# Sheet1.net
KiCad netlist of a schematic drawn in Altium Designer
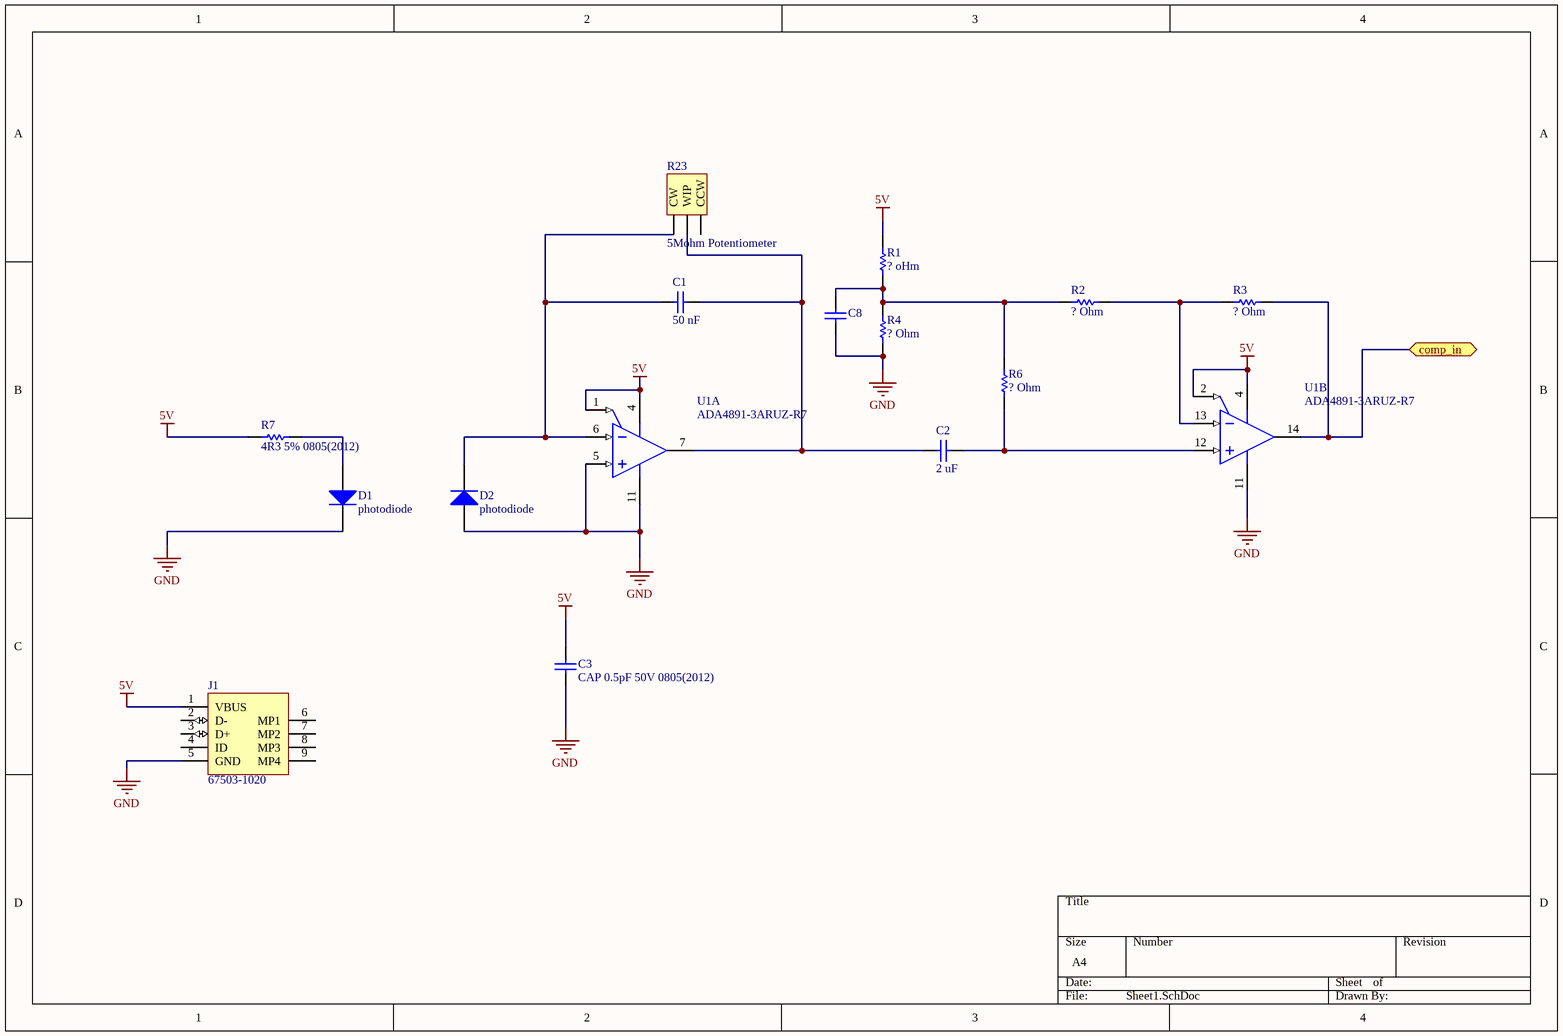
[diagram p0: Sheet1.SchDoc]

(export (version "E")
  (design (tool "Eeschema 10.0.6"))
  (components
    (comp (ref "C1")
      (value "50 nF")
      (footprint "CAPC0805(2012)75_M")
      (description "CAP 0.5pF 50V ±0.1pF 0805 (2012 Metric) Thickness 0.75mm SMD")
      (fields (field (name "TOLERANCE") "Â±0.1pF"))
      (libsource (lib "Altium Content Vault") (part "CMP-1036-00018-1"))
    )
    (comp (ref "C2")
      (value "2 uF")
      (footprint "CAPC0805(2012)75_M")
      (description "CAP 0.5pF 50V ±0.1pF 0805 (2012 Metric) Thickness 0.75mm SMD")
      (fields (field (name "TOLERANCE") "Â±0.1pF"))
      (libsource (lib "Altium Content Vault") (part "CMP-1036-00018-1"))
    )
    (comp (ref "C3")
      (value "CAP 0.5pF 50V 0805(2012)")
      (footprint "CAPC0805(2012)75_M")
      (description "CAP 0.5pF 50V ±0.1pF 0805 (2012 Metric) Thickness 0.75mm SMD")
      (fields (field (name "TOLERANCE") "Â±0.1pF"))
      (libsource (lib "Altium Content Vault") (part "CAP"))
    )
    (comp (ref "C8")
      (value "CAP 0.5pF 50V 0805(2012)")
      (footprint "CAPC0805(2012)75_M")
      (description "CAP 0.5pF 50V ±0.1pF 0805 (2012 Metric) Thickness 0.75mm SMD")
      (fields (field (name "TOLERANCE") "Â±0.1pF"))
      (libsource (lib "Altium Content Vault") (part "CMP-1036-00018-1"))
    )
    (comp (ref "D1")
      (value "photodiode")
      (footprint "3mm_diode")
      (libsource (lib "HeartbeatLibrary") (part "photodiode"))
    )
    (comp (ref "D2")
      (value "photodiode")
      (footprint "3mm_diode")
      (libsource (lib "HeartbeatLibrary") (part "photodiode"))
    )
    (comp (ref "J1")
      (value "67503-1020")
      (footprint "MOLX-67503-1020_V")
      (description "USB, MINI, SMD, RA KME04-USBMU03A01")
      (fields (field (name "MANUFACTURER") "Molex"))
      (libsource (lib "Altium Content Vault") (part "MOLX-67503-1020"))
    )
    (comp (ref "R1")
      (value "? oHm")
      (footprint "RESC0805(2012)_M")
      (description "4R3 0.125W 5% 0805 (2012 Metric)  SMD")
      (fields (field (name "TOLERANCE") "5 %") (field (name "POWER") "0.125 W"))
      (libsource (lib "Altium Content Vault") (part "RES"))
    )
    (comp (ref "R2")
      (value "? Ohm")
      (footprint "RESC0805(2012)_M")
      (description "4R3 0.125W 5% 0805 (2012 Metric)  SMD")
      (fields (field (name "TOLERANCE") "5 %") (field (name "POWER") "0.125 W"))
      (libsource (lib "Altium Content Vault") (part "RES"))
    )
    (comp (ref "R3")
      (value "? Ohm")
      (footprint "RESC0805(2012)_M")
      (description "4R3 0.125W 5% 0805 (2012 Metric)  SMD")
      (fields (field (name "TOLERANCE") "5 %") (field (name "POWER") "0.125 W"))
      (libsource (lib "Altium Content Vault") (part "CMP-1013-00017-1"))
    )
    (comp (ref "R4")
      (value "? Ohm")
      (footprint "RESC0805(2012)_M")
      (description "4R3 0.125W 5% 0805 (2012 Metric)  SMD")
      (fields (field (name "TOLERANCE") "5 %") (field (name "POWER") "0.125 W"))
      (libsource (lib "Altium Content Vault") (part "RES"))
    )
    (comp (ref "R6")
      (value "? Ohm")
      (footprint "RESC0805(2012)_M")
      (description "4R3 0.125W 5% 0805 (2012 Metric)  SMD")
      (fields (field (name "TOLERANCE") "5 %") (field (name "POWER") "0.125 W"))
      (libsource (lib "Altium Content Vault") (part "RES"))
    )
    (comp (ref "R7")
      (value "4R3 5% 0805(2012)")
      (footprint "RESC0805(2012)_M")
      (description "4R3 0.125W 5% 0805 (2012 Metric)  SMD")
      (fields (field (name "TOLERANCE") "5 %") (field (name "POWER") "0.125 W"))
      (libsource (lib "Altium Content Vault") (part "RES"))
    )
    (comp (ref "R23")
      (value "5Mohm Potentiometer")
      (footprint "5k_pot")
      (description "3296W-1-505LF")
      (libsource (lib "HeartbeatLibrary") (part "5Mohm Potentiometer"))
    )
    (comp (ref "U1")
      (value "ADA4891-3ARUZ-R7")
      (footprint "ADI-RU-14_L")
      (fields (field (name "GENERIC PART NUMBER") "ADA4891-3") (field (name "MANUFACTURER") "Analog Devices"))
      (libsource (lib "Altium Content Vault") (part "CMP-0384-01869-1"))
    )
  )
  (nets
    (net (code "1") (name "/comp_in") (class "Default")
      (node (ref "R3") (pin "2") (pinfunction "2_2") (pintype "passive"))
      (node (ref "U1") (pin "14") (pinfunction "OUT_2_14") (pintype "tri_state"))
    )
    (net (code "2") (name "5V") (class "Default")
      (node (ref "C3") (pin "2") (pinfunction "2_2") (pintype "passive"))
      (node (ref "J1") (pin "1") (pinfunction "VBUS_1") (pintype "power_in"))
      (node (ref "R1") (pin "2") (pinfunction "2_2") (pintype "passive"))
      (node (ref "R7") (pin "2") (pinfunction "2_2") (pintype "passive"))
      (node (ref "U1") (pin "1") (pinfunction "~{PD1}_1") (pintype "input"))
      (node (ref "U1") (pin "2") (pinfunction "~{PD2}_2") (pintype "input"))
      (node (ref "U1") (pin "4") (pinfunction "+VS_4") (pintype "power_in"))
    )
    (net (code "3") (name "GND") (class "Default")
      (node (ref "C3") (pin "1") (pinfunction "1_1") (pintype "passive"))
      (node (ref "C8") (pin "1") (pinfunction "1_1") (pintype "passive"))
      (node (ref "D1") (pin "2") (pinfunction "K_2") (pintype "passive"))
      (node (ref "D2") (pin "1") (pinfunction "A_1") (pintype "passive"))
      (node (ref "J1") (pin "5") (pinfunction "GND_5") (pintype "power_in"))
      (node (ref "R4") (pin "1") (pinfunction "1_1") (pintype "passive"))
      (node (ref "U1") (pin "11") (pinfunction "-VS_11") (pintype "power_in"))
      (node (ref "U1") (pin "5") (pinfunction "+IN_1_5") (pintype "input"))
    )
    (net (code "4") (name "Net-(C8-Pad2)") (class "Default")
      (node (ref "C8") (pin "2") (pinfunction "2_2") (pintype "passive"))
      (node (ref "R1") (pin "1") (pinfunction "1_1") (pintype "passive"))
      (node (ref "R2") (pin "1") (pinfunction "1_1") (pintype "passive"))
      (node (ref "R4") (pin "2") (pinfunction "2_2") (pintype "passive"))
      (node (ref "R6") (pin "2") (pinfunction "2_2") (pintype "passive"))
    )
    (net (code "5") (name "Net-(D1-A)") (class "Default")
      (node (ref "D1") (pin "1") (pinfunction "A_1") (pintype "passive"))
      (node (ref "R7") (pin "1") (pinfunction "1_1") (pintype "passive"))
    )
    (net (code "6") (name "Net-(D2-K)") (class "Default")
      (node (ref "C1") (pin "2") (pinfunction "2_2") (pintype "passive"))
      (node (ref "D2") (pin "2") (pinfunction "K_2") (pintype "passive"))
      (node (ref "R23") (pin "1") (pinfunction "CW_1") (pintype "passive"))
      (node (ref "U1") (pin "6") (pinfunction "-IN_1_6") (pintype "input"))
    )
    (net (code "7") (name "Net-(R23-WIP)") (class "Default")
      (node (ref "C1") (pin "1") (pinfunction "1_1") (pintype "passive"))
      (node (ref "C2") (pin "2") (pinfunction "2_2") (pintype "passive"))
      (node (ref "R23") (pin "2") (pinfunction "WIP_2") (pintype "passive"))
      (node (ref "U1") (pin "7") (pinfunction "OUT_1_7") (pintype "tri_state"))
    )
    (net (code "8") (name "Net-(U1B-+IN_2)") (class "Default")
      (node (ref "C2") (pin "1") (pinfunction "1_1") (pintype "passive"))
      (node (ref "R6") (pin "1") (pinfunction "1_1") (pintype "passive"))
      (node (ref "U1") (pin "12") (pinfunction "+IN_2_12") (pintype "input"))
    )
    (net (code "9") (name "Net-(U1B--IN_2)") (class "Default")
      (node (ref "R2") (pin "2") (pinfunction "2_2") (pintype "passive"))
      (node (ref "R3") (pin "1") (pinfunction "1_1") (pintype "passive"))
      (node (ref "U1") (pin "13") (pinfunction "-IN_2_13") (pintype "input"))
    )
    (net (code "10") (name "unconnected-(J1-D+-Pad3)") (class "Default")
      (node (ref "J1") (pin "3") (pinfunction "D+_3") (pintype "bidirectional"))
    )
    (net (code "11") (name "unconnected-(J1-D--Pad2)") (class "Default")
      (node (ref "J1") (pin "2") (pinfunction "D-_2") (pintype "bidirectional"))
    )
    (net (code "12") (name "unconnected-(J1-ID-Pad4)") (class "Default")
      (node (ref "J1") (pin "4") (pinfunction "ID_4") (pintype "passive"))
    )
    (net (code "13") (name "unconnected-(J1-MP1-Pad6)") (class "Default")
      (node (ref "J1") (pin "6") (pinfunction "MP1_6") (pintype "passive"))
    )
    (net (code "14") (name "unconnected-(J1-MP2-Pad7)") (class "Default")
      (node (ref "J1") (pin "7") (pinfunction "MP2_7") (pintype "passive"))
    )
    (net (code "15") (name "unconnected-(J1-MP3-Pad8)") (class "Default")
      (node (ref "J1") (pin "8") (pinfunction "MP3_8") (pintype "passive"))
    )
    (net (code "16") (name "unconnected-(J1-MP4-Pad9)") (class "Default")
      (node (ref "J1") (pin "9") (pinfunction "MP4_9") (pintype "passive"))
    )
    (net (code "17") (name "unconnected-(R23-CCW-Pad3)") (class "Default")
      (node (ref "R23") (pin "3") (pinfunction "CCW_3") (pintype "passive"))
    )
  )
)
